# Sheet1.net
KiCad netlist of a schematic drawn in Altium Designer
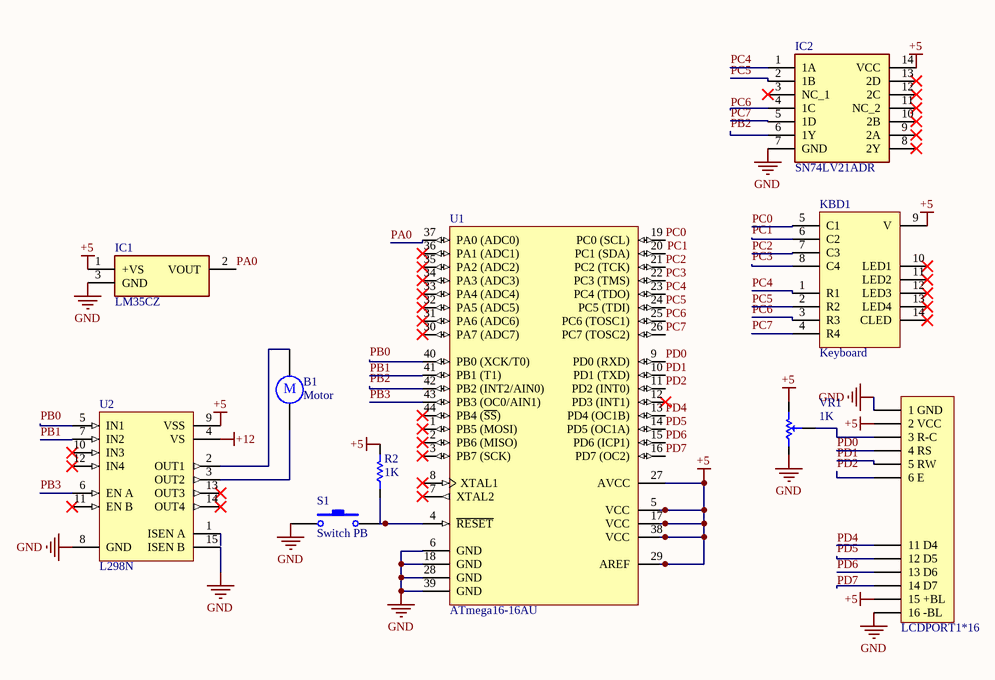
[diagram p0: Sheet1.SchDoc]

(export (version "E")
  (design (tool "Eeschema 10.0.6"))
  (components
    (comp (ref "B1")
      (value "Motor")
      (footprint "RB5-10.5")
      (description "Motor, General Kind")
      (fields (field (name "PUBLISHER") "Altium Limited"))
      (libsource (lib "Miscellaneous Devices") (part "Motor"))
    )
    (comp (ref "IC1")
      (value "LM35CZ")
      (footprint "SamacSys:TO127P254X495-3P")
      (description "Integrated Circuit")
      (fields (field (name "MOUSER PART NUMBER") "926-LM35CZ"))
      (libsource (lib "*") (part "LM35CZ"))
    )
    (comp (ref "IC2")
      (value "SN74LV21ADR")
      (footprint "SamacSys:SOIC127P600X175-14N")
      (description "Integrated Circuit")
      (fields (field (name "MOUSER PART NUMBER") "595-SN74LV21ADR"))
      (libsource (lib "*") (part "SN74LV21ADR"))
    )
    (comp (ref "KBD1")
      (value "Keyboard")
      (footprint "Keyboard")
      (fields (field (name "DESIGNER") "Saeid Jorablo"))
      (libsource (lib "My_Library") (part "Keyboard Matrix 4x4"))
    )
    (comp (ref "LCDPORT1*16")
      (value "LCDPORT1*16")
      (footprint "HDR1X16")
      (description "LCDPORT 1*16; 80mm*36mm")
      (fields (field (name "DESIGNER") "Seyed Mohsen Ghasemain"))
      (libsource (lib "usefully_Library") (part "LCDPORT 1*16"))
    )
    (comp (ref "R2")
      (value "1K")
      (footprint "RES 0805 (2012X06L)")
      (description "Resistor")
      (fields (field (name "TOLERANCE") "5%"))
      (libsource (lib "My_Library") (part "Resistor"))
    )
    (comp (ref "S1")
      (value "Switch PB")
      (footprint "Switch - Push to On")
      (description "Push Button Switch")
      (libsource (lib "My_Library") (part "Switch PB"))
    )
    (comp (ref "U1")
      (value "ATmega16-16AU")
      (footprint "44A_N")
      (libsource (lib "Atmel Microcontroller megaAVR") (part "ATmega16-16AU"))
    )
    (comp (ref "U2")
      (value "L298N")
      (footprint "Multiwatt15H")
      (description "Dual Full Bridge Driver")
      (fields (field (name "PUBLISHER") "Altium Limited"))
      (libsource (lib "My_Library") (part "L298N"))
    )
    (comp (ref "VR1")
      (value "1K")
      (footprint "Pot 00")
      (description "Variable Resistor")
      (fields (field (name "DESIGNER") "Saeid Jorablo"))
      (libsource (lib "My_Library") (part "Resistor Variable"))
    )
  )
  (nets
    (net (code "1") (name "+5") (class "Default")
      (node (ref "IC1") (pin "1") (pinfunction "+VS_1") (pintype "passive"))
      (node (ref "IC2") (pin "14") (pinfunction "VCC_14") (pintype "passive"))
      (node (ref "KBD1") (pin "9") (pinfunction "V_9") (pintype "passive"))
      (node (ref "LCDPORT1*16") (pin "15") (pinfunction "15_+BL_15") (pintype "passive"))
      (node (ref "LCDPORT1*16") (pin "2") (pinfunction "2_VCC_2") (pintype "passive"))
      (node (ref "R2") (pin "2") (pinfunction "2_2") (pintype "passive"))
      (node (ref "U1") (pin "17") (pinfunction "VCC_17") (pintype "power_in"))
      (node (ref "U1") (pin "27") (pinfunction "AVCC_27") (pintype "power_in"))
      (node (ref "U1") (pin "29") (pinfunction "AREF_29") (pintype "power_in"))
      (node (ref "U1") (pin "38") (pinfunction "VCC_38") (pintype "power_in"))
      (node (ref "U1") (pin "5") (pinfunction "VCC_5") (pintype "power_in"))
      (node (ref "U2") (pin "9") (pinfunction "VSS_9") (pintype "power_in"))
      (node (ref "VR1") (pin "2") (pinfunction "CW_2") (pintype "passive"))
    )
    (net (code "2") (name "+12") (class "Default")
      (node (ref "U2") (pin "4") (pinfunction "VS_4") (pintype "power_in"))
    )
    (net (code "3") (name "/PA0") (class "Default")
      (node (ref "IC1") (pin "2") (pinfunction "VOUT_2") (pintype "passive"))
      (node (ref "U1") (pin "37") (pinfunction "PA0_(ADC0)_37") (pintype "bidirectional"))
    )
    (net (code "4") (name "/PB0") (class "Default")
      (node (ref "U1") (pin "40") (pinfunction "PB0_(XCK/T0)_40") (pintype "bidirectional"))
      (node (ref "U2") (pin "5") (pinfunction "IN1_5") (pintype "input"))
    )
    (net (code "5") (name "/PB1") (class "Default")
      (node (ref "U2") (pin "7") (pinfunction "IN2_7") (pintype "input"))
    )
    (net (code "6") (name "/PB2") (class "Default")
      (node (ref "IC2") (pin "6") (pinfunction "1Y_6") (pintype "passive"))
      (node (ref "U1") (pin "42") (pinfunction "PB2_(INT2/AIN0)_42") (pintype "bidirectional"))
    )
    (net (code "7") (name "/PB3") (class "Default")
      (node (ref "U1") (pin "43") (pinfunction "PB3_(OC0/AIN1)_43") (pintype "bidirectional"))
      (node (ref "U2") (pin "6") (pinfunction "EN_A_6") (pintype "input"))
    )
    (net (code "8") (name "/PC0") (class "Default")
      (node (ref "KBD1") (pin "5") (pinfunction "C1_5") (pintype "passive"))
      (node (ref "U1") (pin "19") (pinfunction "PC0_(SCL)_19") (pintype "bidirectional"))
    )
    (net (code "9") (name "/PC1") (class "Default")
      (node (ref "KBD1") (pin "6") (pinfunction "C2_6") (pintype "passive"))
    )
    (net (code "10") (name "/PC2") (class "Default")
      (node (ref "KBD1") (pin "7") (pinfunction "C3_7") (pintype "passive"))
      (node (ref "U1") (pin "21") (pinfunction "PC2_(TCK)_21") (pintype "bidirectional"))
    )
    (net (code "11") (name "/PC3") (class "Default")
      (node (ref "KBD1") (pin "8") (pinfunction "C4_8") (pintype "passive"))
      (node (ref "U1") (pin "22") (pinfunction "PC3_(TMS)_22") (pintype "bidirectional"))
    )
    (net (code "12") (name "/PC4") (class "Default")
      (node (ref "IC2") (pin "1") (pinfunction "1A_1") (pintype "passive"))
      (node (ref "KBD1") (pin "1") (pinfunction "R1_1") (pintype "passive"))
      (node (ref "U1") (pin "23") (pinfunction "PC4_(TDO)_23") (pintype "bidirectional"))
    )
    (net (code "13") (name "/PC5") (class "Default")
      (node (ref "IC2") (pin "2") (pinfunction "1B_2") (pintype "passive"))
      (node (ref "KBD1") (pin "2") (pinfunction "R2_2") (pintype "passive"))
      (node (ref "U1") (pin "24") (pinfunction "PC5_(TDI)_24") (pintype "bidirectional"))
    )
    (net (code "14") (name "/PC6") (class "Default")
      (node (ref "IC2") (pin "4") (pinfunction "1C_4") (pintype "passive"))
      (node (ref "KBD1") (pin "3") (pinfunction "R3_3") (pintype "passive"))
      (node (ref "U1") (pin "25") (pinfunction "PC6_(TOSC1)_25") (pintype "bidirectional"))
    )
    (net (code "15") (name "/PC7") (class "Default")
      (node (ref "IC2") (pin "5") (pinfunction "1D_5") (pintype "passive"))
      (node (ref "KBD1") (pin "4") (pinfunction "R4_4") (pintype "passive"))
      (node (ref "U1") (pin "26") (pinfunction "PC7_(TOSC2)_26") (pintype "bidirectional"))
    )
    (net (code "16") (name "/PD0") (class "Default")
      (node (ref "LCDPORT1*16") (pin "4") (pinfunction "4_RS_4") (pintype "passive"))
      (node (ref "U1") (pin "9") (pinfunction "PD0_(RXD)_9") (pintype "bidirectional"))
    )
    (net (code "17") (name "/PD1") (class "Default")
      (node (ref "LCDPORT1*16") (pin "5") (pinfunction "5_RW_5") (pintype "passive"))
      (node (ref "U1") (pin "10") (pinfunction "PD1_(TXD)_10") (pintype "bidirectional"))
    )
    (net (code "18") (name "/PD2") (class "Default")
      (node (ref "LCDPORT1*16") (pin "6") (pinfunction "6_E_6") (pintype "passive"))
      (node (ref "U1") (pin "11") (pinfunction "PD2_(INT0)_11") (pintype "bidirectional"))
    )
    (net (code "19") (name "/PD4") (class "Default")
      (node (ref "LCDPORT1*16") (pin "11") (pinfunction "11_D4_11") (pintype "passive"))
      (node (ref "U1") (pin "13") (pinfunction "PD4_(OC1B)_13") (pintype "bidirectional"))
    )
    (net (code "20") (name "/PD5") (class "Default")
      (node (ref "LCDPORT1*16") (pin "12") (pinfunction "12_D5_12") (pintype "passive"))
      (node (ref "U1") (pin "14") (pinfunction "PD5_(OC1A)_14") (pintype "bidirectional"))
    )
    (net (code "21") (name "/PD6") (class "Default")
      (node (ref "LCDPORT1*16") (pin "13") (pinfunction "13_D6_13") (pintype "passive"))
      (node (ref "U1") (pin "15") (pinfunction "PD6_(ICP1)_15") (pintype "bidirectional"))
    )
    (net (code "22") (name "/PD7") (class "Default")
      (node (ref "LCDPORT1*16") (pin "14") (pinfunction "14_D7_14") (pintype "passive"))
      (node (ref "U1") (pin "16") (pinfunction "PD7_(OC2)_16") (pintype "bidirectional"))
    )
    (net (code "23") (name "GND") (class "Default")
      (node (ref "IC1") (pin "3") (pinfunction "GND_3") (pintype "passive"))
      (node (ref "IC2") (pin "7") (pinfunction "GND_7") (pintype "passive"))
      (node (ref "LCDPORT1*16") (pin "1") (pinfunction "1_GND_1") (pintype "passive"))
      (node (ref "LCDPORT1*16") (pin "16") (pinfunction "16_-BL_16") (pintype "passive"))
      (node (ref "S1") (pin "1") (pinfunction "1_1") (pintype "passive"))
      (node (ref "U1") (pin "18") (pinfunction "GND_18") (pintype "power_in"))
      (node (ref "U1") (pin "28") (pinfunction "GND_28") (pintype "power_in"))
      (node (ref "U1") (pin "39") (pinfunction "GND_39") (pintype "power_in"))
      (node (ref "U1") (pin "6") (pinfunction "GND_6") (pintype "power_in"))
      (node (ref "U2") (pin "15") (pinfunction "ISEN_B_15") (pintype "passive"))
      (node (ref "U2") (pin "8") (pinfunction "GND_8") (pintype "power_in"))
      (node (ref "VR1") (pin "1") (pinfunction "CCW_1") (pintype "passive"))
    )
    (net (code "24") (name "Net-(LCDPORT1*16-3_R-C)") (class "Default")
      (node (ref "LCDPORT1*16") (pin "3") (pinfunction "3_R-C_3") (pintype "passive"))
      (node (ref "VR1") (pin "3") (pinfunction "Setpoint_3") (pintype "passive"))
    )
    (net (code "25") (name "Net-(U1-~{RESET})") (class "Default")
      (node (ref "R2") (pin "1") (pinfunction "1_1") (pintype "passive"))
      (node (ref "S1") (pin "2") (pinfunction "2_2") (pintype "passive"))
      (node (ref "U1") (pin "4") (pinfunction "~{RESET}_4") (pintype "input"))
    )
    (net (code "26") (name "Net-(U2-OUT1)") (class "Default")
      (node (ref "B1") (pin "1") (pinfunction "1_1") (pintype "passive"))
      (node (ref "U2") (pin "2") (pinfunction "OUT1_2") (pintype "output"))
    )
    (net (code "27") (name "Net-(U2-OUT2)") (class "Default")
      (node (ref "B1") (pin "2") (pinfunction "2_2") (pintype "passive"))
      (node (ref "U2") (pin "3") (pinfunction "OUT2_3") (pintype "output"))
    )
    (net (code "28") (name "unconnected-(IC2-2A-Pad9)") (class "Default")
      (node (ref "IC2") (pin "9") (pinfunction "2A_9") (pintype "passive+no_connect"))
    )
    (net (code "29") (name "unconnected-(IC2-2B-Pad10)") (class "Default")
      (node (ref "IC2") (pin "10") (pinfunction "2B_10") (pintype "passive+no_connect"))
    )
    (net (code "30") (name "unconnected-(IC2-2C-Pad12)") (class "Default")
      (node (ref "IC2") (pin "12") (pinfunction "2C_12") (pintype "passive+no_connect"))
    )
    (net (code "31") (name "unconnected-(IC2-2D-Pad13)") (class "Default")
      (node (ref "IC2") (pin "13") (pinfunction "2D_13") (pintype "passive+no_connect"))
    )
    (net (code "32") (name "unconnected-(IC2-2Y-Pad8)") (class "Default")
      (node (ref "IC2") (pin "8") (pinfunction "2Y_8") (pintype "passive+no_connect"))
    )
    (net (code "33") (name "unconnected-(IC2-NC_1-Pad3)") (class "Default")
      (node (ref "IC2") (pin "3") (pinfunction "NC_1_3") (pintype "passive+no_connect"))
    )
    (net (code "34") (name "unconnected-(IC2-NC_2-Pad11)") (class "Default")
      (node (ref "IC2") (pin "11") (pinfunction "NC_2_11") (pintype "passive+no_connect"))
    )
    (net (code "35") (name "unconnected-(KBD1-CLED-Pad14)") (class "Default")
      (node (ref "KBD1") (pin "14") (pinfunction "CLED_14") (pintype "passive+no_connect"))
    )
    (net (code "36") (name "unconnected-(KBD1-LED1-Pad10)") (class "Default")
      (node (ref "KBD1") (pin "10") (pinfunction "LED1_10") (pintype "passive+no_connect"))
    )
    (net (code "37") (name "unconnected-(KBD1-LED2-Pad11)") (class "Default")
      (node (ref "KBD1") (pin "11") (pinfunction "LED2_11") (pintype "passive+no_connect"))
    )
    (net (code "38") (name "unconnected-(KBD1-LED3-Pad12)") (class "Default")
      (node (ref "KBD1") (pin "12") (pinfunction "LED3_12") (pintype "passive+no_connect"))
    )
    (net (code "39") (name "unconnected-(KBD1-LED4-Pad13)") (class "Default")
      (node (ref "KBD1") (pin "13") (pinfunction "LED4_13") (pintype "passive+no_connect"))
    )
    (net (code "40") (name "unconnected-(U1-PA1_(ADC1)-Pad36)") (class "Default")
      (node (ref "U1") (pin "36") (pinfunction "PA1_(ADC1)_36") (pintype "bidirectional+no_connect"))
    )
    (net (code "41") (name "unconnected-(U1-PA2_(ADC2)-Pad35)") (class "Default")
      (node (ref "U1") (pin "35") (pinfunction "PA2_(ADC2)_35") (pintype "bidirectional+no_connect"))
    )
    (net (code "42") (name "unconnected-(U1-PA3_(ADC3)-Pad34)") (class "Default")
      (node (ref "U1") (pin "34") (pinfunction "PA3_(ADC3)_34") (pintype "bidirectional+no_connect"))
    )
    (net (code "43") (name "unconnected-(U1-PA4_(ADC4)-Pad33)") (class "Default")
      (node (ref "U1") (pin "33") (pinfunction "PA4_(ADC4)_33") (pintype "bidirectional+no_connect"))
    )
    (net (code "44") (name "unconnected-(U1-PA5_(ADC5)-Pad32)") (class "Default")
      (node (ref "U1") (pin "32") (pinfunction "PA5_(ADC5)_32") (pintype "bidirectional+no_connect"))
    )
    (net (code "45") (name "unconnected-(U1-PA6_(ADC6)-Pad31)") (class "Default")
      (node (ref "U1") (pin "31") (pinfunction "PA6_(ADC6)_31") (pintype "bidirectional+no_connect"))
    )
    (net (code "46") (name "unconnected-(U1-PA7_(ADC7)-Pad30)") (class "Default")
      (node (ref "U1") (pin "30") (pinfunction "PA7_(ADC7)_30") (pintype "bidirectional+no_connect"))
    )
    (net (code "47") (name "unconnected-(U1-PB1_(T1)-Pad41)") (class "Default")
      (node (ref "U1") (pin "41") (pinfunction "PB1_(T1)_41") (pintype "bidirectional"))
    )
    (net (code "48") (name "unconnected-(U1-PB4_(~{SS})-Pad44)") (class "Default")
      (node (ref "U1") (pin "44") (pinfunction "PB4_(~{SS})_44") (pintype "bidirectional+no_connect"))
    )
    (net (code "49") (name "unconnected-(U1-PB5_(MOSI)-Pad1)") (class "Default")
      (node (ref "U1") (pin "1") (pinfunction "PB5_(MOSI)_1") (pintype "bidirectional+no_connect"))
    )
    (net (code "50") (name "unconnected-(U1-PB6_(MISO)-Pad2)") (class "Default")
      (node (ref "U1") (pin "2") (pinfunction "PB6_(MISO)_2") (pintype "bidirectional+no_connect"))
    )
    (net (code "51") (name "unconnected-(U1-PB7_(SCK)-Pad3)") (class "Default")
      (node (ref "U1") (pin "3") (pinfunction "PB7_(SCK)_3") (pintype "bidirectional+no_connect"))
    )
    (net (code "52") (name "unconnected-(U1-PC1_(SDA)-Pad20)") (class "Default")
      (node (ref "U1") (pin "20") (pinfunction "PC1_(SDA)_20") (pintype "bidirectional"))
    )
    (net (code "53") (name "unconnected-(U1-PD3_(INT1)-Pad12)") (class "Default")
      (node (ref "U1") (pin "12") (pinfunction "PD3_(INT1)_12") (pintype "bidirectional+no_connect"))
    )
    (net (code "54") (name "unconnected-(U1-XTAL1-Pad8)") (class "Default")
      (node (ref "U1") (pin "8") (pinfunction "XTAL1_8") (pintype "input+no_connect"))
    )
    (net (code "55") (name "unconnected-(U1-XTAL2-Pad7)") (class "Default")
      (node (ref "U1") (pin "7") (pinfunction "XTAL2_7") (pintype "output+no_connect"))
    )
    (net (code "56") (name "unconnected-(U2-EN_B-Pad11)") (class "Default")
      (node (ref "U2") (pin "11") (pinfunction "EN_B_11") (pintype "input+no_connect"))
    )
    (net (code "57") (name "unconnected-(U2-IN3-Pad10)") (class "Default")
      (node (ref "U2") (pin "10") (pinfunction "IN3_10") (pintype "input+no_connect"))
    )
    (net (code "58") (name "unconnected-(U2-IN4-Pad12)") (class "Default")
      (node (ref "U2") (pin "12") (pinfunction "IN4_12") (pintype "input+no_connect"))
    )
    (net (code "59") (name "unconnected-(U2-ISEN_A-Pad1)") (class "Default")
      (node (ref "U2") (pin "1") (pinfunction "ISEN_A_1") (pintype "passive"))
    )
    (net (code "60") (name "unconnected-(U2-OUT3-Pad13)") (class "Default")
      (node (ref "U2") (pin "13") (pinfunction "OUT3_13") (pintype "output+no_connect"))
    )
    (net (code "61") (name "unconnected-(U2-OUT4-Pad14)") (class "Default")
      (node (ref "U2") (pin "14") (pinfunction "OUT4_14") (pintype "output+no_connect"))
    )
  )
)
